# Fri3D_2018_CONTROLLER_01.net
KiCad netlist of a schematic drawn in Altium Designer
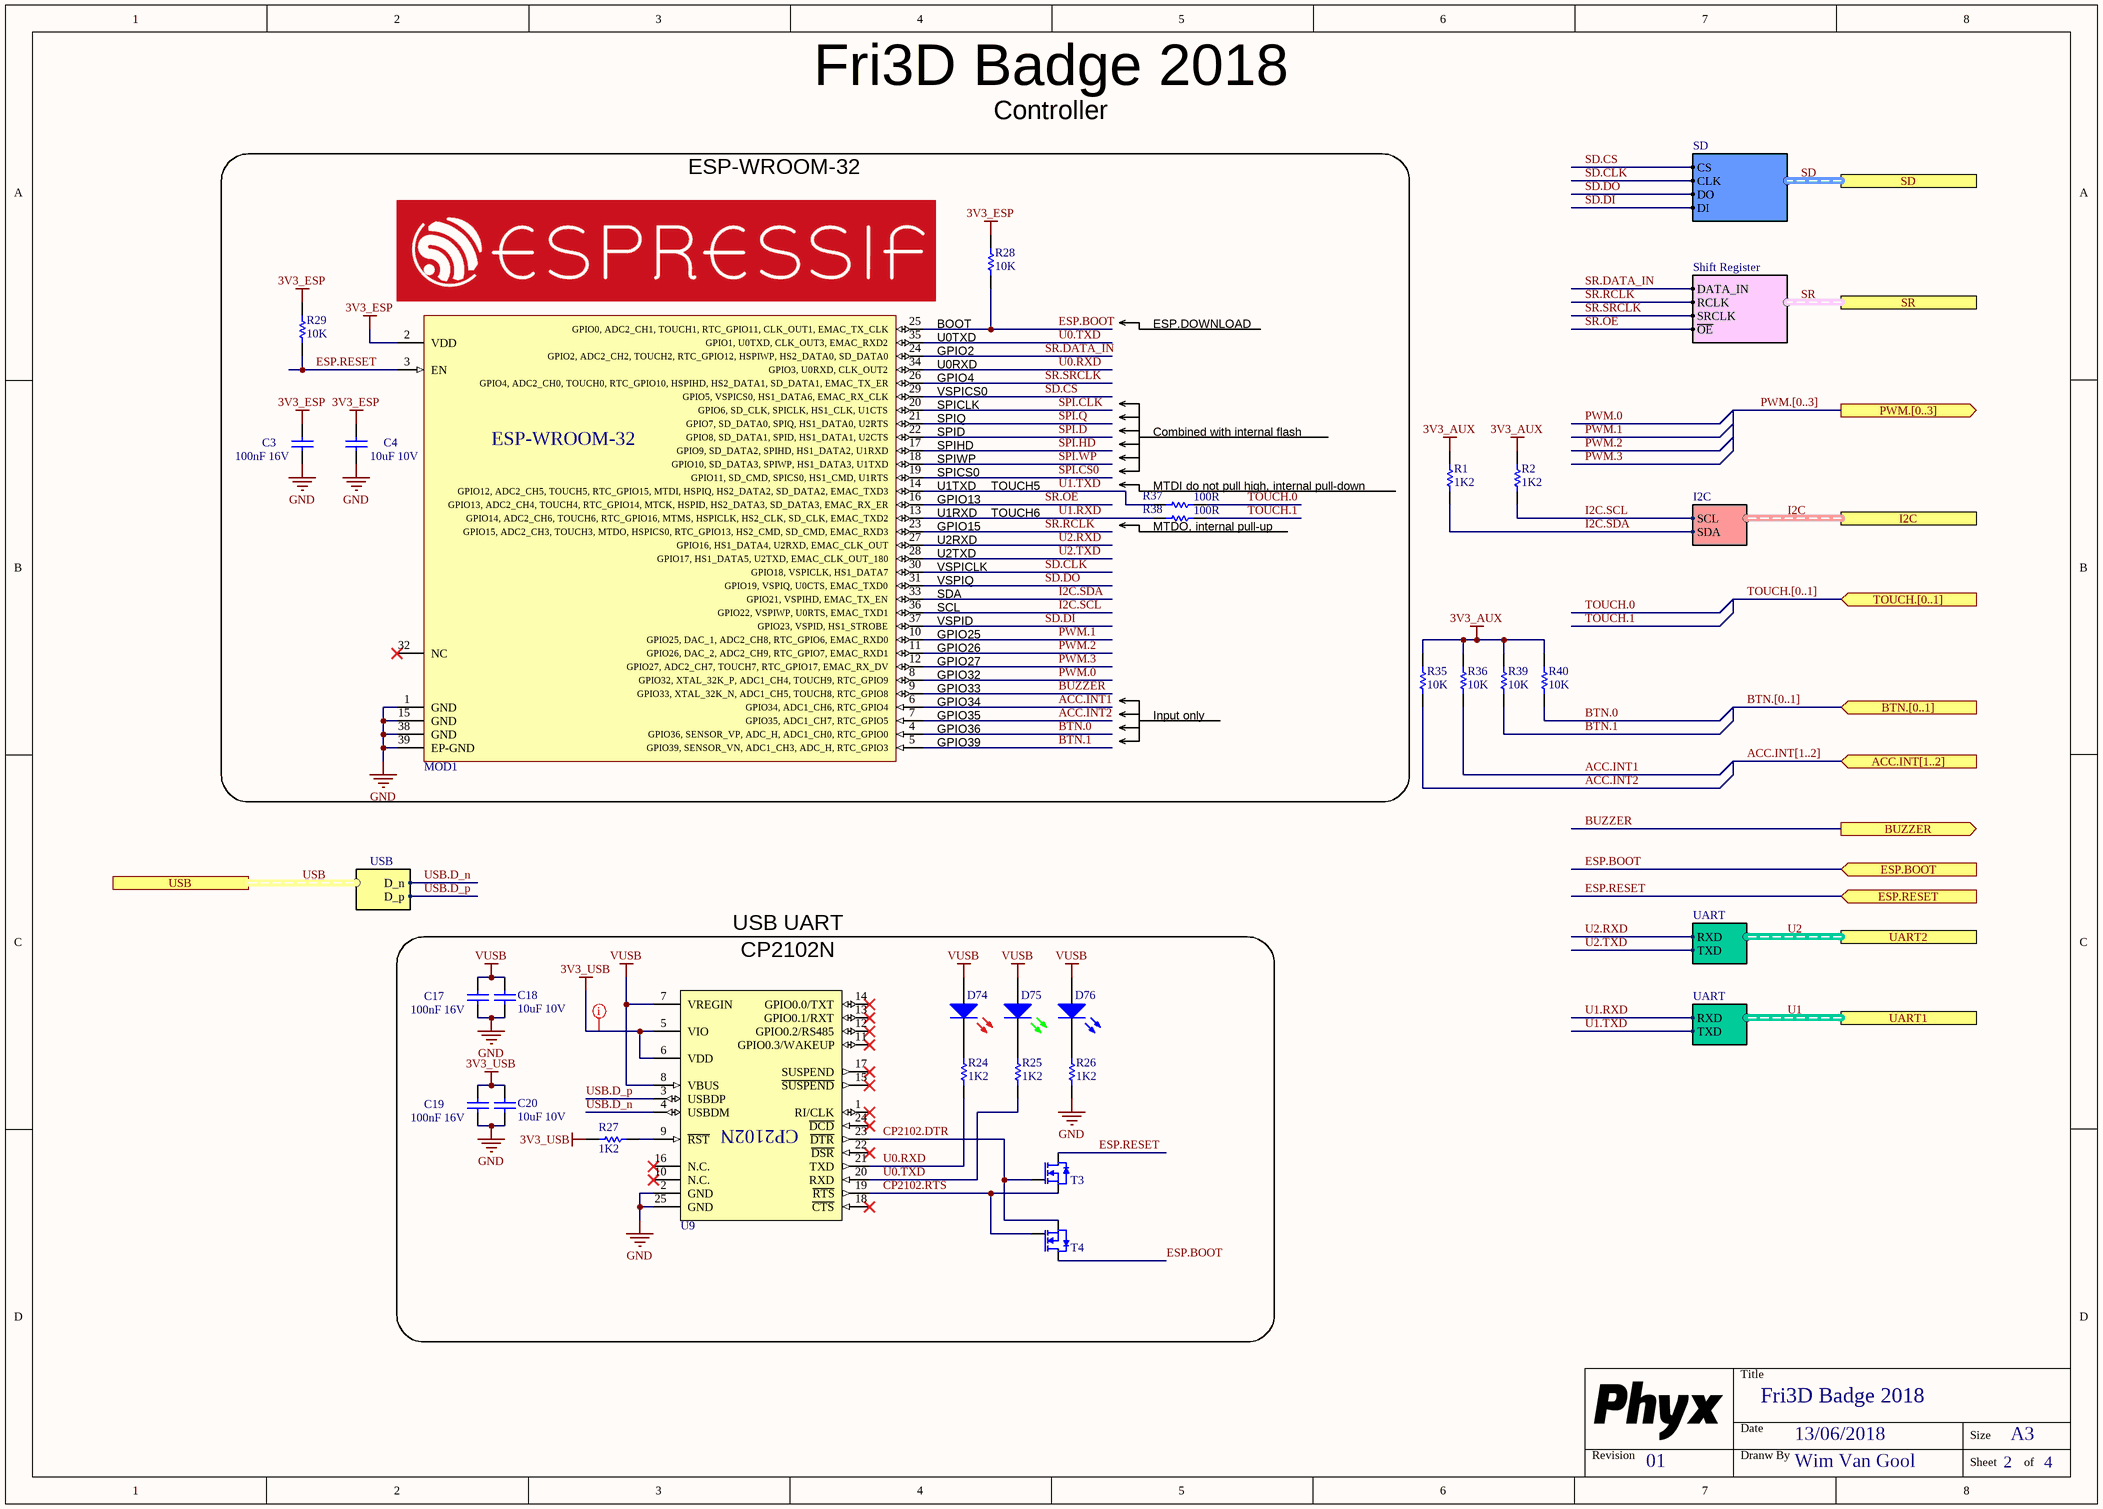
[diagram p0: Fri3D_2018_CONTROLLER_01.SchDoc]

(export (version "E")
  (design (tool "Eeschema 10.0.6"))
  (components
    (comp (ref "C3")
      (value "100nF 16V")
      (footprint "C0603_N")
      (description "Capacitor Ceramic")
      (libsource (lib "Phyx_Components") (part "CAP_CERAMIC"))
    )
    (comp (ref "C4")
      (value "10uF 10V")
      (footprint "C0805_N")
      (description "Capacitor Ceramic")
      (fields (field (name "Comment") "CAP_CERAMIC"))
      (libsource (lib "Phyx_Components") (part "CAP_CERAMIC"))
    )
    (comp (ref "C17")
      (value "100nF 16V")
      (footprint "C0603_N")
      (description "Capacitor Ceramic")
      (libsource (lib "Phyx_Components") (part "CAP_CERAMIC"))
    )
    (comp (ref "C18")
      (value "10uF 10V")
      (footprint "C0805_N")
      (description "Capacitor Ceramic")
      (fields (field (name "Comment") "CAP_CERAMIC"))
      (libsource (lib "Phyx_Components") (part "CAP_CERAMIC"))
    )
    (comp (ref "C19")
      (value "100nF 16V")
      (footprint "C0603_N")
      (description "Capacitor Ceramic")
      (libsource (lib "Phyx_Components") (part "CAP_CERAMIC"))
    )
    (comp (ref "C20")
      (value "10uF 10V")
      (footprint "C0805_N")
      (description "Capacitor Ceramic")
      (fields (field (name "Comment") "CAP_CERAMIC"))
      (libsource (lib "Phyx_Components") (part "CAP_CERAMIC"))
    )
    (comp (ref "D74")
      (value "Default 0805 Red LED")
      (footprint "LED_0805_RD")
      (description "=Description")
      (libsource (lib "Phyx_Components") (part "LED_RED"))
    )
    (comp (ref "D75")
      (value "Default 0805 Green LED")
      (footprint "LED_0805_GR")
      (description "=Description")
      (libsource (lib "Phyx_Components") (part "LED_GREEN"))
    )
    (comp (ref "D76")
      (value "Default 0805 Blue LED")
      (footprint "LED_0805_BL")
      (description "=Description")
      (libsource (lib "Phyx_Components") (part "LED_BLUE"))
    )
    (comp (ref "MOD1")
      (value "ESP-32 based ESP-WROOM-32")
      (footprint "ESP-WROOM-32")
      (description "WiFi # MOD ESP-WROOM-32")
      (libsource (lib "Phyx_Components") (part "ESP-WROOM-32"))
    )
    (comp (ref "R1")
      (value "1K2")
      (footprint "R0603_N")
      (fields (field (name "Comment") "RESISTOR"))
      (libsource (lib "Phyx_Components") (part "RESISTOR"))
    )
    (comp (ref "R2")
      (value "1K2")
      (footprint "R0603_N")
      (fields (field (name "Comment") "RESISTOR"))
      (libsource (lib "Phyx_Components") (part "RESISTOR"))
    )
    (comp (ref "R24")
      (value "1K2")
      (footprint "R0603_N")
      (fields (field (name "Comment") "RESISTOR"))
      (libsource (lib "Phyx_Components") (part "RESISTOR"))
    )
    (comp (ref "R25")
      (value "1K2")
      (footprint "R0603_N")
      (fields (field (name "Comment") "RESISTOR"))
      (libsource (lib "Phyx_Components") (part "RESISTOR"))
    )
    (comp (ref "R26")
      (value "1K2")
      (footprint "R0603_N")
      (fields (field (name "Comment") "RESISTOR"))
      (libsource (lib "Phyx_Components") (part "RESISTOR"))
    )
    (comp (ref "R27")
      (value "1K2")
      (footprint "R0603_N")
      (fields (field (name "Comment") "RESISTOR"))
      (libsource (lib "Phyx_Components") (part "RESISTOR"))
    )
    (comp (ref "R28")
      (value "10K")
      (footprint "R0603_N")
      (fields (field (name "Comment") "RESISTOR"))
      (libsource (lib "Phyx_Components") (part "RESISTOR"))
    )
    (comp (ref "R29")
      (value "10K")
      (footprint "R0603_N")
      (fields (field (name "Comment") "RESISTOR"))
      (libsource (lib "Phyx_Components") (part "RESISTOR"))
    )
    (comp (ref "R35")
      (value "10K")
      (footprint "R0603_N")
      (fields (field (name "Comment") "RESISTOR"))
      (libsource (lib "Phyx_Components") (part "RESISTOR"))
    )
    (comp (ref "R36")
      (value "10K")
      (footprint "R0603_N")
      (fields (field (name "Comment") "RESISTOR"))
      (libsource (lib "Phyx_Components") (part "RESISTOR"))
    )
    (comp (ref "R37")
      (value "100R")
      (footprint "R0603_N")
      (fields (field (name "Comment") "RESISTOR"))
      (libsource (lib "Phyx_Components") (part "RESISTOR"))
    )
    (comp (ref "R38")
      (value "100R")
      (footprint "R0603_N")
      (fields (field (name "Comment") "RESISTOR"))
      (libsource (lib "Phyx_Components") (part "RESISTOR"))
    )
    (comp (ref "R39")
      (value "10K")
      (footprint "R0603_N")
      (fields (field (name "Comment") "RESISTOR"))
      (libsource (lib "Phyx_Components") (part "RESISTOR"))
    )
    (comp (ref "R40")
      (value "10K")
      (footprint "R0603_N")
      (fields (field (name "Comment") "RESISTOR"))
      (libsource (lib "Phyx_Components") (part "RESISTOR"))
    )
    (comp (ref "T3")
      (value "0.2A N-Ch MOSFET Vgs 3.2")
      (footprint "SOT23-3")
      (libsource (lib "Phyx_Components") (part "N_MOSFET_GSD"))
    )
    (comp (ref "T4")
      (value "0.2A N-Ch MOSFET Vgs 3.2")
      (footprint "SOT23-3")
      (libsource (lib "Phyx_Components") (part "N_MOSFET_GSD"))
    )
    (comp (ref "U9")
      (value "USB to UART 3.3-5V")
      (footprint "QFN_24")
      (description "=Description")
      (libsource (lib "Phyx_Components") (part "CP2102N_QFN24"))
    )
  )
  (nets
    (net (code "8") (name "/ACC.INT1") (class "Default")
      (node (ref "MOD1") (pin "6") (pinfunction "GPIO34,_ADC1_CH6,_RTC_GPIO4_6") (pintype "input"))
      (node (ref "R36") (pin "2") (pinfunction "2_2") (pintype "passive"))
    )
    (net (code "9") (name "/ACC.INT2") (class "Default")
      (node (ref "MOD1") (pin "7") (pinfunction "GPIO35,_ADC1_CH7,_RTC_GPIO5_7") (pintype "input"))
      (node (ref "R35") (pin "2") (pinfunction "2_2") (pintype "passive"))
    )
    (net (code "11") (name "/BTN.0") (class "Default")
      (node (ref "MOD1") (pin "4") (pinfunction "GPIO36,_SENSOR_VP,_ADC_H,_ADC1_CH0,_RTC_GPIO0_4") (pintype "input"))
      (node (ref "R40") (pin "2") (pinfunction "2_2") (pintype "passive"))
    )
    (net (code "12") (name "/BTN.1") (class "Default")
      (node (ref "MOD1") (pin "5") (pinfunction "GPIO39,_SENSOR_VN,_ADC1_CH3,_ADC_H,_RTC_GPIO3_5") (pintype "input"))
      (node (ref "R39") (pin "2") (pinfunction "2_2") (pintype "passive"))
    )
    (net (code "14") (name "/BUZZER") (class "Default")
      (node (ref "MOD1") (pin "9") (pinfunction "GPIO33,_XTAL_32K_N,_ADC1_CH5,_TOUCH8,_RTC_GPIO8_9") (pintype "bidirectional"))
    )
    (net (code "15") (name "/CP2102.DTR") (class "Default")
      (node (ref "T3") (pin "1") (pinfunction "G_1") (pintype "passive"))
      (node (ref "T4") (pin "2") (pinfunction "S_2") (pintype "passive"))
      (node (ref "U9") (pin "23") (pinfunction "~{DTR}_23") (pintype "output"))
    )
    (net (code "16") (name "/CP2102.RTS") (class "Default")
      (node (ref "T3") (pin "2") (pinfunction "S_2") (pintype "passive"))
      (node (ref "T4") (pin "1") (pinfunction "G_1") (pintype "passive"))
      (node (ref "U9") (pin "19") (pinfunction "~{RTS}_19") (pintype "output"))
    )
    (net (code "17") (name "/ESP.BOOT") (class "Default")
      (node (ref "MOD1") (pin "25") (pinfunction "GPIO0,_ADC2_CH1,_TOUCH1,_RTC_GPIO11,_CLK_OUT1,_EMAC_TX_CLK_25") (pintype "bidirectional"))
      (node (ref "R28") (pin "2") (pinfunction "2_2") (pintype "passive"))
      (node (ref "T4") (pin "3") (pinfunction "D_3") (pintype "passive"))
    )
    (net (code "18") (name "/ESP.RESET") (class "Default")
      (node (ref "MOD1") (pin "3") (pinfunction "EN_3") (pintype "input"))
      (node (ref "R29") (pin "2") (pinfunction "2_2") (pintype "passive"))
      (node (ref "T3") (pin "3") (pinfunction "D_3") (pintype "passive"))
    )
    (net (code "19") (name "/I2C.SCL") (class "Default")
      (node (ref "MOD1") (pin "36") (pinfunction "GPIO22,_VSPIWP,_U0RTS,_EMAC_TXD1_36") (pintype "bidirectional"))
      (node (ref "R2") (pin "2") (pinfunction "2_2") (pintype "passive"))
    )
    (net (code "20") (name "/I2C.SDA") (class "Default")
      (node (ref "MOD1") (pin "33") (pinfunction "GPIO21,_VSPIHD,_EMAC_TX_EN_33") (pintype "bidirectional"))
      (node (ref "R1") (pin "2") (pinfunction "2_2") (pintype "passive"))
    )
    (net (code "22") (name "/PWM.0") (class "Default")
      (node (ref "MOD1") (pin "8") (pinfunction "GPIO32,_XTAL_32K_P,_ADC1_CH4,_TOUCH9,_RTC_GPIO9_8") (pintype "bidirectional"))
    )
    (net (code "23") (name "/PWM.1") (class "Default")
      (node (ref "MOD1") (pin "10") (pinfunction "GPIO25,_DAC_1,_ADC2_CH8,_RTC_GPIO6,_EMAC_RXD0_10") (pintype "bidirectional"))
    )
    (net (code "24") (name "/PWM.2") (class "Default")
      (node (ref "MOD1") (pin "11") (pinfunction "GPIO26,_DAC_2,_ADC2_CH9,_RTC_GPIO7,_EMAC_RXD1_11") (pintype "bidirectional"))
    )
    (net (code "25") (name "/PWM.3") (class "Default")
      (node (ref "MOD1") (pin "12") (pinfunction "GPIO27,_ADC2_CH7,_TOUCH7,_RTC_GPIO17,_EMAC_RX_DV_12") (pintype "bidirectional"))
    )
    (net (code "27") (name "/SD.CLK") (class "Default")
      (node (ref "MOD1") (pin "30") (pinfunction "GPIO18,_VSPICLK,_HS1_DATA7_30") (pintype "bidirectional"))
    )
    (net (code "28") (name "/SD.CS") (class "Default")
      (node (ref "MOD1") (pin "29") (pinfunction "GPIO5,_VSPICS0,_HS1_DATA6,_EMAC_RX_CLK_29") (pintype "bidirectional"))
    )
    (net (code "29") (name "/SD.DI") (class "Default")
      (node (ref "MOD1") (pin "37") (pinfunction "GPIO23,_VSPID,_HS1_STROBE_37") (pintype "bidirectional"))
    )
    (net (code "30") (name "/SD.DO") (class "Default")
      (node (ref "MOD1") (pin "31") (pinfunction "GPIO19,_VSPIQ,_U0CTS,_EMAC_TXD0_31") (pintype "bidirectional"))
    )
    (net (code "32") (name "/SPI.CLK") (class "Default")
      (node (ref "MOD1") (pin "20") (pinfunction "GPIO6,_SD_CLK,_SPICLK,_HS1_CLK,_U1CTS_20") (pintype "bidirectional"))
    )
    (net (code "33") (name "/SPI.CS0") (class "Default")
      (node (ref "MOD1") (pin "19") (pinfunction "GPIO11,_SD_CMD,_SPICS0,_HS1_CMD,_U1RTS_19") (pintype "bidirectional"))
    )
    (net (code "34") (name "/SPI.D") (class "Default")
      (node (ref "MOD1") (pin "22") (pinfunction "GPIO8,_SD_DATA1,_SPID,_HS1_DATA1,_U2CTS_22") (pintype "bidirectional"))
    )
    (net (code "35") (name "/SPI.HD") (class "Default")
      (node (ref "MOD1") (pin "17") (pinfunction "GPIO9,_SD_DATA2,_SPIHD,_HS1_DATA2,_U1RXD_17") (pintype "bidirectional"))
    )
    (net (code "36") (name "/SPI.Q") (class "Default")
      (node (ref "MOD1") (pin "21") (pinfunction "GPIO7,_SD_DATA0,_SPIQ,_HS1_DATA0,_U2RTS_21") (pintype "bidirectional"))
    )
    (net (code "37") (name "/SPI.WP") (class "Default")
      (node (ref "MOD1") (pin "18") (pinfunction "GPIO10,_SD_DATA3,_SPIWP,_HS1_DATA3,_U1TXD_18") (pintype "bidirectional"))
    )
    (net (code "38") (name "/SR.DATA_IN") (class "Default")
      (node (ref "MOD1") (pin "24") (pinfunction "GPIO2,_ADC2_CH2,_TOUCH2,_RTC_GPIO12,_HSPIWP,_HS2_DATA0,_SD_DATA0_24") (pintype "bidirectional"))
    )
    (net (code "39") (name "/SR.RCLK") (class "Default")
      (node (ref "MOD1") (pin "23") (pinfunction "GPIO15,_ADC2_CH3,_TOUCH3,_MTDO,_HSPICS0,_RTC_GPIO13,_HS2_CMD,_SD_CMD,_EMAC_RXD3_23") (pintype "bidirectional"))
    )
    (net (code "40") (name "/SR.SRCLK") (class "Default")
      (node (ref "MOD1") (pin "26") (pinfunction "GPIO4,_ADC2_CH0,_TOUCH0,_RTC_GPIO10,_HSPIHD,_HS2_DATA1,_SD_DATA1,_EMAC_TX_ER_26") (pintype "bidirectional"))
    )
    (net (code "41") (name "/SR.~{OE}") (class "Default")
      (node (ref "MOD1") (pin "16") (pinfunction "GPIO13,_ADC2_CH4,_TOUCH4,_RTC_GPIO14,_MTCK,_HSPID,_HS2_DATA3,_SD_DATA3,_EMAC_RX_ER_16") (pintype "bidirectional"))
    )
    (net (code "43") (name "/TOUCH.0") (class "Default")
      (node (ref "R37") (pin "2") (pinfunction "2_2") (pintype "passive"))
    )
    (net (code "44") (name "/TOUCH.1") (class "Default")
      (node (ref "R38") (pin "2") (pinfunction "2_2") (pintype "passive"))
    )
    (net (code "46") (name "/U0.RXD") (class "Default")
      (node (ref "MOD1") (pin "34") (pinfunction "GPIO3,_U0RXD,_CLK_OUT2_34") (pintype "bidirectional"))
      (node (ref "R24") (pin "2") (pinfunction "2_2") (pintype "passive"))
      (node (ref "U9") (pin "21") (pinfunction "TXD_21") (pintype "output"))
    )
    (net (code "47") (name "/U0.TXD") (class "Default")
      (node (ref "MOD1") (pin "35") (pinfunction "GPIO1,_U0TXD,_CLK_OUT3,_EMAC_RXD2_35") (pintype "bidirectional"))
      (node (ref "R25") (pin "2") (pinfunction "2_2") (pintype "passive"))
      (node (ref "U9") (pin "20") (pinfunction "RXD_20") (pintype "input"))
    )
    (net (code "48") (name "/U1.RXD") (class "Default")
      (node (ref "MOD1") (pin "13") (pinfunction "GPIO14,_ADC2_CH6,_TOUCH6,_RTC_GPIO16,_MTMS,_HSPICLK,_HS2_CLK,_SD_CLK,_EMAC_TXD2_13") (pintype "bidirectional"))
      (node (ref "R38") (pin "1") (pinfunction "1_1") (pintype "passive"))
    )
    (net (code "49") (name "/U1.TXD") (class "Default")
      (node (ref "MOD1") (pin "14") (pinfunction "GPIO12,_ADC2_CH5,_TOUCH5,_RTC_GPIO15,_MTDI,_HSPIQ,_HS2_DATA2,_SD_DATA2,_EMAC_TXD3_14") (pintype "bidirectional"))
      (node (ref "R37") (pin "1") (pinfunction "1_1") (pintype "passive"))
    )
    (net (code "51") (name "/U2.RXD") (class "Default")
      (node (ref "MOD1") (pin "27") (pinfunction "GPIO16,_HS1_DATA4,_U2RXD,_EMAC_CLK_OUT_27") (pintype "bidirectional"))
    )
    (net (code "52") (name "/U2.TXD") (class "Default")
      (node (ref "MOD1") (pin "28") (pinfunction "GPIO17,_HS1_DATA5,_U2TXD,_EMAC_CLK_OUT_180_28") (pintype "bidirectional"))
    )
    (net (code "54") (name "/USB.D_n") (class "Default")
      (node (ref "U9") (pin "4") (pinfunction "USBDM_4") (pintype "bidirectional"))
    )
    (net (code "55") (name "/USB.D_p") (class "Default")
      (node (ref "U9") (pin "3") (pinfunction "USBDP_3") (pintype "bidirectional"))
    )
    (net (code "57") (name "3V3_AUX") (class "Default")
      (node (ref "R1") (pin "1") (pinfunction "1_1") (pintype "passive"))
      (node (ref "R2") (pin "1") (pinfunction "1_1") (pintype "passive"))
      (node (ref "R35") (pin "1") (pinfunction "1_1") (pintype "passive"))
      (node (ref "R36") (pin "1") (pinfunction "1_1") (pintype "passive"))
      (node (ref "R39") (pin "1") (pinfunction "1_1") (pintype "passive"))
      (node (ref "R40") (pin "1") (pinfunction "1_1") (pintype "passive"))
    )
    (net (code "58") (name "3V3_ESP") (class "Default")
      (node (ref "C3") (pin "1") (pinfunction "1_1") (pintype "passive"))
      (node (ref "C4") (pin "1") (pinfunction "1_1") (pintype "passive"))
      (node (ref "MOD1") (pin "2") (pinfunction "VDD_2") (pintype "power_in"))
      (node (ref "R28") (pin "1") (pinfunction "1_1") (pintype "passive"))
      (node (ref "R29") (pin "1") (pinfunction "1_1") (pintype "passive"))
    )
    (net (code "59") (name "3V3_USB") (class "Default")
      (node (ref "C19") (pin "1") (pinfunction "1_1") (pintype "passive"))
      (node (ref "C20") (pin "2") (pinfunction "2_2") (pintype "passive"))
      (node (ref "R27") (pin "1") (pinfunction "1_1") (pintype "passive"))
      (node (ref "U9") (pin "5") (pinfunction "VIO_5") (pintype "power_in"))
      (node (ref "U9") (pin "6") (pinfunction "VDD_6") (pintype "power_in"))
    )
    (net (code "60") (name "GND") (class "Default")
      (node (ref "C17") (pin "2") (pinfunction "2_2") (pintype "passive"))
      (node (ref "C18") (pin "1") (pinfunction "1_1") (pintype "passive"))
      (node (ref "C19") (pin "2") (pinfunction "2_2") (pintype "passive"))
      (node (ref "C20") (pin "1") (pinfunction "1_1") (pintype "passive"))
      (node (ref "C3") (pin "2") (pinfunction "2_2") (pintype "passive"))
      (node (ref "C4") (pin "2") (pinfunction "2_2") (pintype "passive"))
      (node (ref "MOD1") (pin "1") (pinfunction "GND_1") (pintype "power_in"))
      (node (ref "MOD1") (pin "15") (pinfunction "GND_15") (pintype "power_in"))
      (node (ref "MOD1") (pin "38") (pinfunction "GND_38") (pintype "power_in"))
      (node (ref "MOD1") (pin "39") (pinfunction "EP-GND_39") (pintype "power_in"))
      (node (ref "R26") (pin "2") (pinfunction "2_2") (pintype "passive"))
      (node (ref "U9") (pin "2") (pinfunction "GND_2") (pintype "power_in"))
      (node (ref "U9") (pin "25") (pinfunction "GND_25") (pintype "power_in"))
    )
    (net (code "61") (name "Net-(D74-K)") (class "Default")
      (node (ref "D74") (pin "2") (pinfunction "K_2") (pintype "passive"))
      (node (ref "R24") (pin "1") (pinfunction "1_1") (pintype "passive"))
    )
    (net (code "62") (name "Net-(D75-K)") (class "Default")
      (node (ref "D75") (pin "2") (pinfunction "K_2") (pintype "passive"))
      (node (ref "R25") (pin "1") (pinfunction "1_1") (pintype "passive"))
    )
    (net (code "63") (name "Net-(D76-K)") (class "Default")
      (node (ref "D76") (pin "2") (pinfunction "K_2") (pintype "passive"))
      (node (ref "R26") (pin "1") (pinfunction "1_1") (pintype "passive"))
    )
    (net (code "64") (name "Net-(U9-~{RST})") (class "Default")
      (node (ref "R27") (pin "2") (pinfunction "2_2") (pintype "passive"))
      (node (ref "U9") (pin "9") (pinfunction "~{RST}_9") (pintype "input"))
    )
    (net (code "65") (name "VUSB") (class "Default")
      (node (ref "C17") (pin "1") (pinfunction "1_1") (pintype "passive"))
      (node (ref "C18") (pin "2") (pinfunction "2_2") (pintype "passive"))
      (node (ref "D74") (pin "1") (pinfunction "A_1") (pintype "passive"))
      (node (ref "D75") (pin "1") (pinfunction "A_1") (pintype "passive"))
      (node (ref "D76") (pin "1") (pinfunction "A_1") (pintype "passive"))
      (node (ref "U9") (pin "7") (pinfunction "VREGIN_7") (pintype "power_in"))
      (node (ref "U9") (pin "8") (pinfunction "VBUS_8") (pintype "input"))
    )
    (net (code "66") (name "unconnected-(MOD1-NC-Pad32)") (class "Default")
      (node (ref "MOD1") (pin "32") (pinfunction "NC_32") (pintype "passive+no_connect"))
    )
    (net (code "67") (name "unconnected-(U9-GPIO0.0{slash}TXT-Pad14)") (class "Default")
      (node (ref "U9") (pin "14") (pinfunction "GPIO0.0/TXT_14") (pintype "bidirectional+no_connect"))
    )
    (net (code "68") (name "unconnected-(U9-GPIO0.1{slash}RXT-Pad13)") (class "Default")
      (node (ref "U9") (pin "13") (pinfunction "GPIO0.1/RXT_13") (pintype "bidirectional+no_connect"))
    )
    (net (code "69") (name "unconnected-(U9-GPIO0.2{slash}RS485-Pad12)") (class "Default")
      (node (ref "U9") (pin "12") (pinfunction "GPIO0.2/RS485_12") (pintype "bidirectional+no_connect"))
    )
    (net (code "70") (name "unconnected-(U9-GPIO0.3{slash}WAKEUP-Pad11)") (class "Default")
      (node (ref "U9") (pin "11") (pinfunction "GPIO0.3/WAKEUP_11") (pintype "bidirectional+no_connect"))
    )
    (net (code "71") (name "unconnected-(U9-N.C.-Pad10)") (class "Default")
      (node (ref "U9") (pin "10") (pinfunction "N.C._10") (pintype "passive+no_connect"))
    )
    (net (code "72") (name "unconnected-(U9-N.C.-Pad16)") (class "Default")
      (node (ref "U9") (pin "16") (pinfunction "N.C._16") (pintype "passive+no_connect"))
    )
    (net (code "73") (name "unconnected-(U9-RI{slash}CLK-Pad1)") (class "Default")
      (node (ref "U9") (pin "1") (pinfunction "RI/CLK_1") (pintype "bidirectional+no_connect"))
    )
    (net (code "74") (name "unconnected-(U9-SUSPEND-Pad17)") (class "Default")
      (node (ref "U9") (pin "17") (pinfunction "SUSPEND_17") (pintype "output+no_connect"))
    )
    (net (code "75") (name "unconnected-(U9-~{CTS}-Pad18)") (class "Default")
      (node (ref "U9") (pin "18") (pinfunction "~{CTS}_18") (pintype "input+no_connect"))
    )
    (net (code "76") (name "unconnected-(U9-~{DCD}-Pad24)") (class "Default")
      (node (ref "U9") (pin "24") (pinfunction "~{DCD}_24") (pintype "input+no_connect"))
    )
    (net (code "77") (name "unconnected-(U9-~{DSR}-Pad22)") (class "Default")
      (node (ref "U9") (pin "22") (pinfunction "~{DSR}_22") (pintype "input+no_connect"))
    )
    (net (code "78") (name "unconnected-(U9-~{SUSPEND}-Pad15)") (class "Default")
      (node (ref "U9") (pin "15") (pinfunction "~{SUSPEND}_15") (pintype "output+no_connect"))
    )
  )
)
